# Extern.net
KiCad netlist of a schematic drawn in Altium Designer
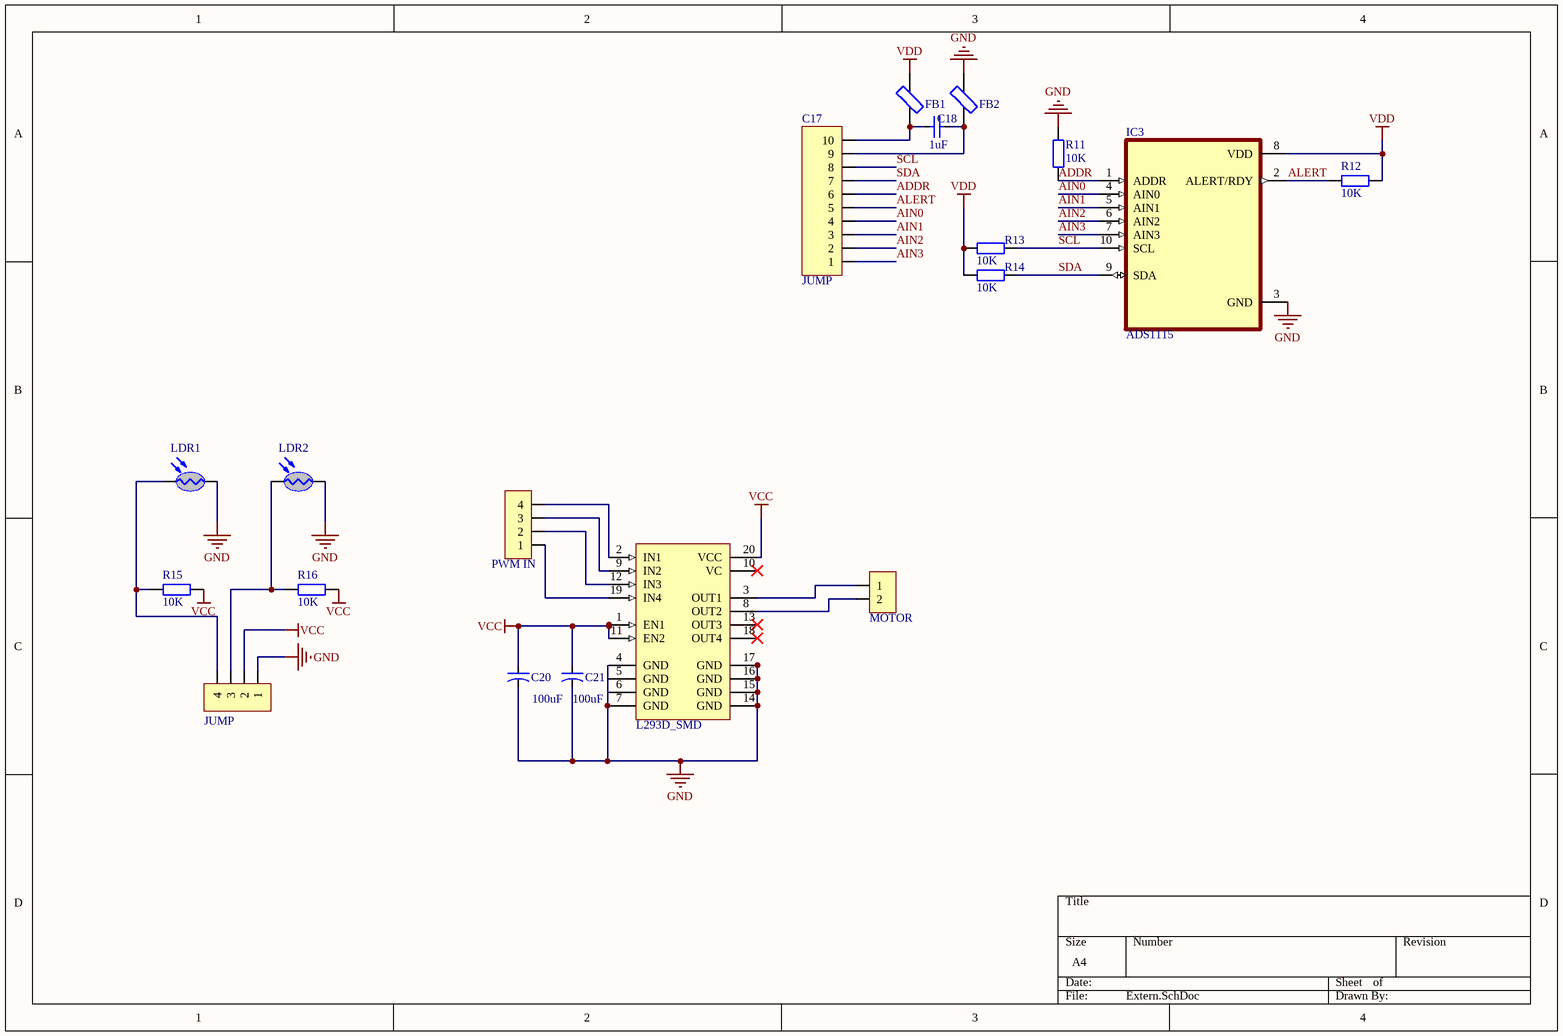
[diagram p0: Extern.SchDoc]

(export (version "E")
  (design (tool "Eeschema 10.0.6"))
  (components
    (comp (ref "C17")
      (value "JUMP")
      (footprint "JP10-C1T")
      (description "WR-PHD 2.54 mm Angled Socket Header")
      (fields
        (field (name "MANUFACTURER") "Würth Elektronik eiSos GmbH")
        (field (name "PARTNO") "613010143121")
        (field (name "CREATED BY") "Karrer Zheng")
      )
      (libsource (lib "My Library") (part "JP10"))
    )
    (comp (ref "C18")
      (value "1uF")
      (footprint "CAP_0402")
      (description "Capacitor")
      (fields (field (name "PUBLISHER") "Altium Limited"))
      (libsource (lib "My Library") (part "CapSMD"))
    )
    (comp (ref "C19")
      (value "PWM IN")
      (footprint "JP4-C1T")
      (description "WR-PHD 2.54 mm Angled Socket Header")
      (fields
        (field (name "MANUFACTURER") "Würth Elektronik eiSos GmbH")
        (field (name "PARTNO") "613004143121")
        (field (name "CREATED BY") "Karrer Zheng")
      )
      (libsource (lib "My Library") (part "JP4"))
    )
    (comp (ref "C20")
      (value "100uF")
      (footprint "CA-ALU-2.54")
      (description "Capacitor (Semiconductor SIM Model)")
      (fields (field (name "PUBLISHER") "Altium Limited"))
      (libsource (lib "My Library") (part "CAP-ALU-DIP"))
    )
    (comp (ref "C21")
      (value "100uF")
      (footprint "CA-ALU-2.54")
      (description "Capacitor (Semiconductor SIM Model)")
      (fields (field (name "PUBLISHER") "Altium Limited"))
      (libsource (lib "My Library") (part "CAP-ALU-DIP"))
    )
    (comp (ref "C22")
      (value "JUMP")
      (footprint "JP4-C1T")
      (description "WR-PHD 2.54 mm Angled Socket Header")
      (fields
        (field (name "MANUFACTURER") "Würth Elektronik eiSos GmbH")
        (field (name "PARTNO") "613004143121")
        (field (name "CREATED BY") "Karrer Zheng")
      )
      (libsource (lib "") (part "JP4_1"))
    )
    (comp (ref "FB1")
      (value "Ferrit Bead")
      (footprint "RES-SMD-0805")
      (description "Generic Ferrit Bead")
      (libsource (lib "My Library") (part "Ferrit Bead"))
    )
    (comp (ref "FB2")
      (value "Ferrit Bead")
      (footprint "RES-SMD-0805")
      (description "Generic Ferrit Bead")
      (libsource (lib "My Library") (part "Ferrit Bead"))
    )
    (comp (ref "IC3")
      (value "ADS1115")
      (footprint "SOP50P490X110-10N")
      (description "16 bits 4 channals ADC IC")
      (libsource (lib "My Library") (part "ADS1115"))
    )
    (comp (ref "J3")
      (value "MOTOR")
      (footprint "JP2-C1T")
      (description "WR-PHD 2.54 mm Angled Socket Header")
      (fields
        (field (name "MANUFACTURER") "Würth Elektronik eiSos GmbH")
        (field (name "PARTNO") "613002143121")
        (field (name "CREATED BY") "Karrer Zheng")
      )
      (libsource (lib "My Library") (part "JP2"))
    )
    (comp (ref "LDR1")
      (value "LDR")
      (footprint "CDS")
      (description "Quang Tro")
      (libsource (lib "My Library") (part "LDR"))
    )
    (comp (ref "LDR2")
      (value "LDR")
      (footprint "CDS")
      (description "Quang Tro")
      (libsource (lib "My Library") (part "LDR"))
    )
    (comp (ref "R11")
      (value "10K")
      (footprint "RES-SMD-0101")
      (description "Resistor SMD")
      (fields
        (field (name "MANUFACTURER") "Generic Components")
        (field (name "PUBLISHER") "Altium Hobart Technology Centre")
      )
      (libsource (lib "My Library") (part "Resistor - SMD"))
    )
    (comp (ref "R12")
      (value "10K")
      (footprint "RES-SMD-0101")
      (description "Resistor SMD")
      (fields
        (field (name "MANUFACTURER") "Generic Components")
        (field (name "PUBLISHER") "Altium Hobart Technology Centre")
      )
      (libsource (lib "My Library") (part "Resistor - SMD"))
    )
    (comp (ref "R13")
      (value "10K")
      (footprint "RES-SMD-0101")
      (description "Resistor SMD")
      (fields
        (field (name "MANUFACTURER") "Generic Components")
        (field (name "PUBLISHER") "Altium Hobart Technology Centre")
      )
      (libsource (lib "My Library") (part "Resistor - SMD"))
    )
    (comp (ref "R14")
      (value "10K")
      (footprint "RES-SMD-0101")
      (description "Resistor SMD")
      (fields
        (field (name "MANUFACTURER") "Generic Components")
        (field (name "PUBLISHER") "Altium Hobart Technology Centre")
      )
      (libsource (lib "My Library") (part "Resistor - SMD"))
    )
    (comp (ref "R15")
      (value "10K")
      (footprint "RES-SMD-0101")
      (description "Resistor SMD")
      (fields
        (field (name "MANUFACTURER") "Generic Components")
        (field (name "PUBLISHER") "Altium Hobart Technology Centre")
      )
      (libsource (lib "My Library") (part "Resistor - SMD"))
    )
    (comp (ref "R16")
      (value "10K")
      (footprint "RES-SMD-0101")
      (description "Resistor SMD")
      (fields
        (field (name "MANUFACTURER") "Generic Components")
        (field (name "PUBLISHER") "Altium Hobart Technology Centre")
      )
      (libsource (lib "My Library") (part "Resistor - SMD"))
    )
    (comp (ref "U3")
      (value "L293D_SMD")
      (footprint "SO20")
      (description "Push-Pull Four Channel Driver With Diode")
      (fields (field (name "PUBLISHER") "Altium Limited"))
      (libsource (lib "My Library") (part "L293D_SMD"))
    )
  )
  (nets
    (net (code "1") (name "/ADDR") (class "Default")
      (node (ref "C17") (pin "6") (pinfunction "6_6") (pintype "passive"))
      (node (ref "IC3") (pin "1") (pinfunction "ADDR_1") (pintype "input"))
      (node (ref "R11") (pin "2") (pinfunction "2_2") (pintype "passive"))
    )
    (net (code "2") (name "/AIN0") (class "Default")
      (node (ref "C17") (pin "4") (pinfunction "4_4") (pintype "passive"))
      (node (ref "IC3") (pin "4") (pinfunction "AIN0_4") (pintype "input"))
    )
    (net (code "3") (name "/AIN1") (class "Default")
      (node (ref "C17") (pin "3") (pinfunction "3_3") (pintype "passive"))
      (node (ref "IC3") (pin "5") (pinfunction "AIN1_5") (pintype "input"))
    )
    (net (code "4") (name "/AIN2") (class "Default")
      (node (ref "C17") (pin "2") (pinfunction "2_2") (pintype "passive"))
      (node (ref "IC3") (pin "6") (pinfunction "AIN2_6") (pintype "input"))
    )
    (net (code "5") (name "/AIN3") (class "Default")
      (node (ref "C17") (pin "1") (pinfunction "1_1") (pintype "passive"))
      (node (ref "IC3") (pin "7") (pinfunction "AIN3_7") (pintype "input"))
    )
    (net (code "6") (name "/ALERT") (class "Default")
      (node (ref "C17") (pin "5") (pinfunction "5_5") (pintype "passive"))
      (node (ref "IC3") (pin "2") (pinfunction "ALERT/RDY_2") (pintype "output"))
      (node (ref "R12") (pin "2") (pinfunction "2_2") (pintype "passive"))
    )
    (net (code "7") (name "/SCL") (class "Default")
      (node (ref "C17") (pin "8") (pinfunction "8_8") (pintype "passive"))
      (node (ref "IC3") (pin "10") (pinfunction "SCL_10") (pintype "input"))
      (node (ref "R13") (pin "1") (pinfunction "1_1") (pintype "passive"))
    )
    (net (code "8") (name "/SDA") (class "Default")
      (node (ref "C17") (pin "7") (pinfunction "7_7") (pintype "passive"))
      (node (ref "IC3") (pin "9") (pinfunction "SDA_9") (pintype "bidirectional"))
      (node (ref "R14") (pin "1") (pinfunction "1_1") (pintype "passive"))
    )
    (net (code "9") (name "GND") (class "Default")
      (node (ref "C20") (pin "2") (pinfunction "2_2") (pintype "passive"))
      (node (ref "C21") (pin "2") (pinfunction "2_2") (pintype "passive"))
      (node (ref "C22") (pin "1") (pinfunction "1_1") (pintype "passive"))
      (node (ref "FB2") (pin "2") (pintype "passive"))
      (node (ref "IC3") (pin "3") (pinfunction "GND_3") (pintype "power_in"))
      (node (ref "LDR1") (pin "1") (pinfunction "A_1") (pintype "passive"))
      (node (ref "LDR2") (pin "1") (pinfunction "A_1") (pintype "passive"))
      (node (ref "R11") (pin "1") (pinfunction "1_1") (pintype "passive"))
      (node (ref "U3") (pin "14") (pinfunction "GND_14") (pintype "power_in"))
      (node (ref "U3") (pin "15") (pinfunction "GND_15") (pintype "power_in"))
      (node (ref "U3") (pin "16") (pinfunction "GND_16") (pintype "power_in"))
      (node (ref "U3") (pin "17") (pinfunction "GND_17") (pintype "power_in"))
      (node (ref "U3") (pin "7") (pinfunction "GND_7") (pintype "power_in"))
    )
    (net (code "10") (name "Net-(C17-Pad9)") (class "Default")
      (node (ref "C17") (pin "9") (pinfunction "9_9") (pintype "passive"))
      (node (ref "C18") (pin "2") (pinfunction "2_2") (pintype "passive"))
      (node (ref "FB2") (pin "1") (pintype "passive"))
    )
    (net (code "11") (name "Net-(C17-Pad10)") (class "Default")
      (node (ref "C17") (pin "10") (pinfunction "10_10") (pintype "passive"))
      (node (ref "C18") (pin "1") (pinfunction "1_1") (pintype "passive"))
      (node (ref "FB1") (pin "1") (pintype "passive"))
    )
    (net (code "12") (name "Net-(LDR1-K)") (class "Default")
      (node (ref "C22") (pin "4") (pinfunction "4_4") (pintype "passive"))
      (node (ref "LDR1") (pin "2") (pinfunction "K_2") (pintype "passive"))
      (node (ref "R15") (pin "2") (pinfunction "2_2") (pintype "passive"))
    )
    (net (code "13") (name "Net-(LDR2-K)") (class "Default")
      (node (ref "C22") (pin "3") (pinfunction "3_3") (pintype "passive"))
      (node (ref "LDR2") (pin "2") (pinfunction "K_2") (pintype "passive"))
      (node (ref "R16") (pin "2") (pinfunction "2_2") (pintype "passive"))
    )
    (net (code "14") (name "Net-(U3-IN1)") (class "Default")
      (node (ref "C19") (pin "4") (pinfunction "4_4") (pintype "passive"))
      (node (ref "U3") (pin "2") (pinfunction "IN1_2") (pintype "input"))
    )
    (net (code "15") (name "Net-(U3-IN2)") (class "Default")
      (node (ref "C19") (pin "3") (pinfunction "3_3") (pintype "passive"))
      (node (ref "U3") (pin "9") (pinfunction "IN2_9") (pintype "input"))
    )
    (net (code "16") (name "Net-(U3-IN3)") (class "Default")
      (node (ref "C19") (pin "2") (pinfunction "2_2") (pintype "passive"))
      (node (ref "U3") (pin "12") (pinfunction "IN3_12") (pintype "input"))
    )
    (net (code "17") (name "Net-(U3-IN4)") (class "Default")
      (node (ref "C19") (pin "1") (pinfunction "1_1") (pintype "passive"))
      (node (ref "U3") (pin "19") (pinfunction "IN4_19") (pintype "input"))
    )
    (net (code "18") (name "Net-(U3-OUT1)") (class "Default")
      (node (ref "J3") (pin "1") (pinfunction "1_1") (pintype "passive"))
      (node (ref "U3") (pin "3") (pinfunction "OUT1_3") (pintype "tri_state"))
    )
    (net (code "19") (name "Net-(U3-OUT2)") (class "Default")
      (node (ref "J3") (pin "2") (pinfunction "2_2") (pintype "passive"))
      (node (ref "U3") (pin "8") (pinfunction "OUT2_8") (pintype "tri_state"))
    )
    (net (code "20") (name "VCC") (class "Default")
      (node (ref "C20") (pin "1") (pinfunction "1_1") (pintype "passive"))
      (node (ref "C21") (pin "1") (pinfunction "1_1") (pintype "passive"))
      (node (ref "C22") (pin "2") (pinfunction "2_2") (pintype "passive"))
      (node (ref "R15") (pin "1") (pinfunction "1_1") (pintype "passive"))
      (node (ref "R16") (pin "1") (pinfunction "1_1") (pintype "passive"))
      (node (ref "U3") (pin "1") (pinfunction "EN1_1") (pintype "input"))
      (node (ref "U3") (pin "11") (pinfunction "EN2_11") (pintype "input"))
      (node (ref "U3") (pin "20") (pinfunction "VCC_20") (pintype "power_in"))
    )
    (net (code "21") (name "VDD") (class "Default")
      (node (ref "FB1") (pin "2") (pintype "passive"))
      (node (ref "IC3") (pin "8") (pinfunction "VDD_8") (pintype "power_in"))
      (node (ref "R12") (pin "1") (pinfunction "1_1") (pintype "passive"))
      (node (ref "R13") (pin "2") (pinfunction "2_2") (pintype "passive"))
      (node (ref "R14") (pin "2") (pinfunction "2_2") (pintype "passive"))
    )
    (net (code "22") (name "unconnected-(U3-GND-Pad4)") (class "Default")
      (node (ref "U3") (pin "4") (pinfunction "GND_4") (pintype "power_in"))
    )
    (net (code "23") (name "unconnected-(U3-GND-Pad5)") (class "Default")
      (node (ref "U3") (pin "5") (pinfunction "GND_5") (pintype "power_in"))
    )
    (net (code "24") (name "unconnected-(U3-GND-Pad6)") (class "Default")
      (node (ref "U3") (pin "6") (pinfunction "GND_6") (pintype "power_in"))
    )
    (net (code "25") (name "unconnected-(U3-OUT3-Pad13)") (class "Default")
      (node (ref "U3") (pin "13") (pinfunction "OUT3_13") (pintype "tri_state+no_connect"))
    )
    (net (code "26") (name "unconnected-(U3-OUT4-Pad18)") (class "Default")
      (node (ref "U3") (pin "18") (pinfunction "OUT4_18") (pintype "tri_state+no_connect"))
    )
    (net (code "27") (name "unconnected-(U3-VC-Pad10)") (class "Default")
      (node (ref "U3") (pin "10") (pinfunction "VC_10") (pintype "power_in+no_connect"))
    )
  )
)
